# ArduinoUNOinBoard.net
KiCad netlist of a schematic drawn in EAGLE
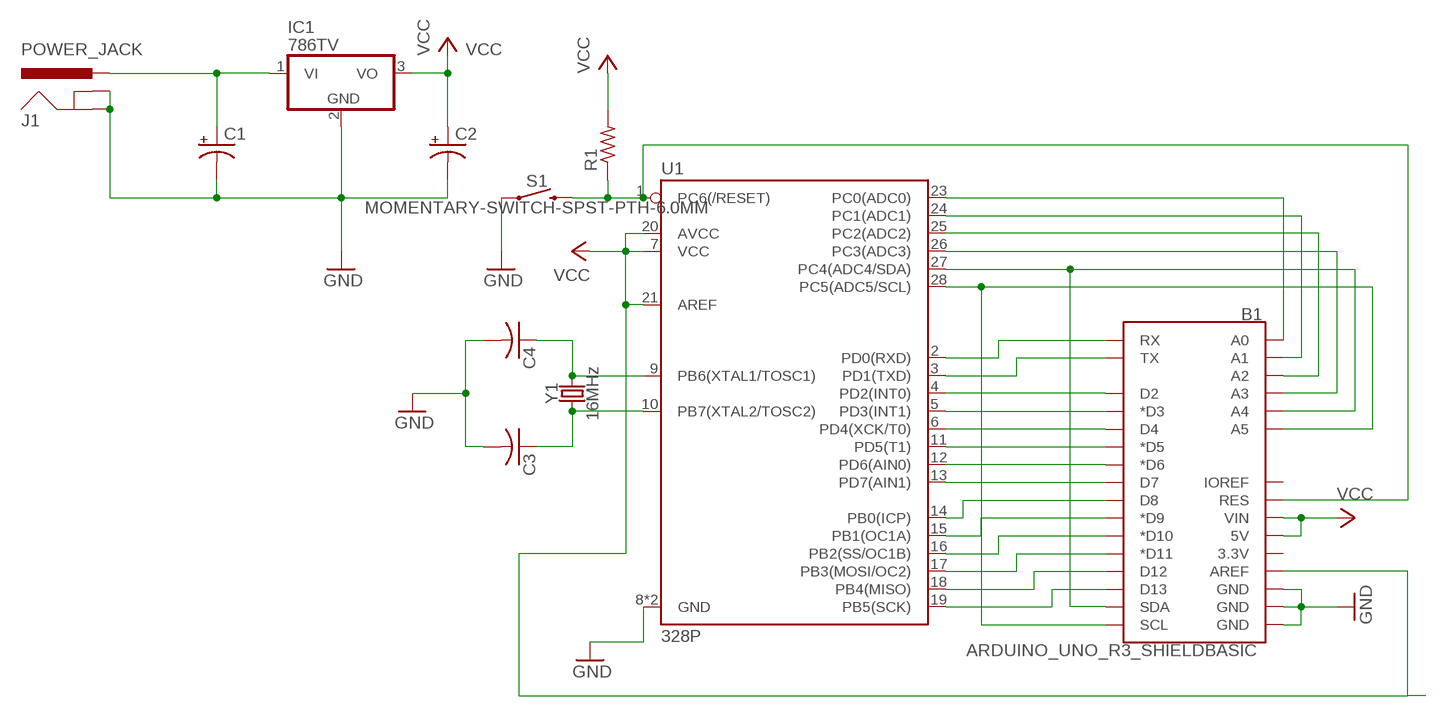
[diagram p0: schematic, sheet 1]

(export (version "E")
  (design (tool "Eeschema 10.0.6"))
  (components
    (comp (ref "B1")
      (value "ARDUINO_UNO_R3_SHIELDBASIC")
      (footprint "eagle-import:UNO_R3_SHIELD")
      (libsource (lib "eagle-import") (part "ARDUINO_UNO_R3_SHIELDBASIC"))
    )
    (comp (ref "C1")
      (value "CPOL-USE2,5-6E")
      (footprint "eagle-import:E2,5-6E")
      (libsource (lib "eagle-import") (part "CPOL-USE2,5-6E"))
    )
    (comp (ref "C2")
      (value "CPOL-USE2,5-6E")
      (footprint "eagle-import:E2,5-6E")
      (libsource (lib "eagle-import") (part "CPOL-USE2,5-6E"))
    )
    (comp (ref "C3")
      (value "C-US025-024X044")
      (footprint "eagle-import:C025-024X044")
      (libsource (lib "eagle-import") (part "C-US025-024X044"))
    )
    (comp (ref "C4")
      (value "C-US025-024X044")
      (footprint "eagle-import:C025-024X044")
      (libsource (lib "eagle-import") (part "C-US025-024X044"))
    )
    (comp (ref "IC1")
      (value "786TV")
      (footprint "eagle-import:TO220V")
      (libsource (lib "eagle-import") (part "78TV6"))
    )
    (comp (ref "J1")
      (value "POWER_JACK")
      (footprint "eagle-import:POWER_JACK_PTH")
      (libsource (lib "eagle-import") (part "POWER_JACK"))
    )
    (comp (ref "R1")
      (value "R-US_0204/7")
      (footprint "eagle-import:0204_7")
      (libsource (lib "eagle-import") (part "R-US_0204/7"))
    )
    (comp (ref "S1")
      (value "MOMENTARY-SWITCH-SPST-PTH-6.0MM")
      (footprint "eagle-import:TACTILE_SWITCH_PTH_6.0MM")
      (libsource (lib "eagle-import") (part "MOMENTARY-SWITCH-SPST-PTH-6.0MM"))
    )
    (comp (ref "U1")
      (value "328P")
      (footprint "eagle-import:DIP28")
      (libsource (lib "eagle-import") (part "ATMEGA328P_PDIP"))
    )
    (comp (ref "Y1")
      (value "16MHz")
      (footprint "eagle-import:HC49US")
      (libsource (lib "eagle-import") (part "CRYSTAL-16MHZPTH-HC49US"))
    )
  )
  (nets
    (net (code "1") (name "GND") (class "Default")
      (node (ref "B1") (pin "GND@0") (pinfunction "GND_GND@0") (pintype "bidirectional"))
      (node (ref "B1") (pin "GND@1") (pinfunction "GND_GND@1") (pintype "bidirectional"))
      (node (ref "B1") (pin "GND@2") (pinfunction "GND_GND@2") (pintype "bidirectional"))
      (node (ref "C1") (pin "-") (pinfunction "-_-") (pintype "passive"))
      (node (ref "C2") (pin "-") (pinfunction "-_-") (pintype "passive"))
      (node (ref "C3") (pin "2") (pinfunction "2_2") (pintype "passive"))
      (node (ref "C4") (pin "2") (pinfunction "2_2") (pintype "passive"))
      (node (ref "IC1") (pin "2") (pinfunction "GND_2") (pintype "passive"))
      (node (ref "J1") (pin "GND") (pinfunction "GND_GND") (pintype "bidirectional"))
      (node (ref "J1") (pin "GNDBREAK") (pinfunction "GNDBREAK_GNDBREAK") (pintype "bidirectional"))
      (node (ref "S1") (pin "1") (pinfunction "1_1") (pintype "passive"))
      (node (ref "U1") (pin "22") (pinfunction "GND_22") (pintype "bidirectional"))
      (node (ref "U1") (pin "8") (pinfunction "GND_8") (pintype "bidirectional"))
    )
    (net (code "2") (name "Net-(B1-*D3)") (class "Default")
      (node (ref "B1") (pin "D3") (pinfunction "*D3_D3") (pintype "bidirectional"))
      (node (ref "U1") (pin "5") (pinfunction "PD3(INT1)_5") (pintype "bidirectional"))
    )
    (net (code "3") (name "Net-(B1-*D5)") (class "Default")
      (node (ref "B1") (pin "D5") (pinfunction "*D5_D5") (pintype "bidirectional"))
      (node (ref "U1") (pin "11") (pinfunction "PD5(T1)_11") (pintype "bidirectional"))
    )
    (net (code "4") (name "Net-(B1-*D6)") (class "Default")
      (node (ref "B1") (pin "D6") (pinfunction "*D6_D6") (pintype "bidirectional"))
      (node (ref "U1") (pin "12") (pinfunction "PD6(AIN0)_12") (pintype "bidirectional"))
    )
    (net (code "5") (name "Net-(B1-*D9)") (class "Default")
      (node (ref "B1") (pin "D9") (pinfunction "*D9_D9") (pintype "bidirectional"))
      (node (ref "U1") (pin "15") (pinfunction "PB1(OC1A)_15") (pintype "bidirectional"))
    )
    (net (code "6") (name "Net-(B1-*D10)") (class "Default")
      (node (ref "B1") (pin "D10") (pinfunction "*D10_D10") (pintype "bidirectional"))
      (node (ref "U1") (pin "16") (pinfunction "PB2(SS/OC1B)_16") (pintype "bidirectional"))
    )
    (net (code "7") (name "Net-(B1-*D11)") (class "Default")
      (node (ref "B1") (pin "D11") (pinfunction "*D11_D11") (pintype "bidirectional"))
      (node (ref "U1") (pin "17") (pinfunction "PB3(MOSI/OC2)_17") (pintype "bidirectional"))
    )
    (net (code "8") (name "Net-(IC1-VI)") (class "Default")
      (node (ref "C1") (pin "+") (pinfunction "+_+") (pintype "passive"))
      (node (ref "IC1") (pin "1") (pinfunction "VI_1") (pintype "input"))
      (node (ref "J1") (pin "PWR") (pinfunction "PWR_PWR") (pintype "bidirectional"))
    )
    (net (code "9") (name "Net-(S1-2)") (class "Default")
      (node (ref "B1") (pin "RES") (pinfunction "RES_RES") (pintype "bidirectional"))
      (node (ref "R1") (pin "1") (pinfunction "1_1") (pintype "passive"))
      (node (ref "S1") (pin "3") (pinfunction "2_3") (pintype "passive"))
      (node (ref "U1") (pin "1") (pinfunction "PC6(/RESET)_1") (pintype "bidirectional"))
    )
    (net (code "10") (name "Net-(U1-PB0(ICP))") (class "Default")
      (node (ref "B1") (pin "D8") (pinfunction "D8_D8") (pintype "bidirectional"))
      (node (ref "U1") (pin "14") (pinfunction "PB0(ICP)_14") (pintype "bidirectional"))
    )
    (net (code "11") (name "Net-(U1-PB4(MISO))") (class "Default")
      (node (ref "B1") (pin "D12") (pinfunction "D12_D12") (pintype "bidirectional"))
      (node (ref "U1") (pin "18") (pinfunction "PB4(MISO)_18") (pintype "bidirectional"))
    )
    (net (code "12") (name "Net-(U1-PB5(SCK))") (class "Default")
      (node (ref "B1") (pin "D13") (pinfunction "D13_D13") (pintype "bidirectional"))
      (node (ref "U1") (pin "19") (pinfunction "PB5(SCK)_19") (pintype "bidirectional"))
    )
    (net (code "13") (name "Net-(U1-PB6(XTAL1{slash}TOSC1))") (class "Default")
      (node (ref "C4") (pin "1") (pinfunction "1_1") (pintype "passive"))
      (node (ref "U1") (pin "9") (pinfunction "PB6(XTAL1/TOSC1)_9") (pintype "bidirectional"))
      (node (ref "Y1") (pin "2") (pinfunction "2_2") (pintype "passive"))
    )
    (net (code "14") (name "Net-(U1-PB7(XTAL2{slash}TOSC2))") (class "Default")
      (node (ref "C3") (pin "1") (pinfunction "1_1") (pintype "passive"))
      (node (ref "U1") (pin "10") (pinfunction "PB7(XTAL2/TOSC2)_10") (pintype "bidirectional"))
      (node (ref "Y1") (pin "1") (pinfunction "1_1") (pintype "passive"))
    )
    (net (code "15") (name "Net-(U1-PC0(ADC0))") (class "Default")
      (node (ref "B1") (pin "A0") (pinfunction "A0_A0") (pintype "bidirectional"))
      (node (ref "U1") (pin "23") (pinfunction "PC0(ADC0)_23") (pintype "bidirectional"))
    )
    (net (code "16") (name "Net-(U1-PC1(ADC1))") (class "Default")
      (node (ref "B1") (pin "A1") (pinfunction "A1_A1") (pintype "bidirectional"))
      (node (ref "U1") (pin "24") (pinfunction "PC1(ADC1)_24") (pintype "bidirectional"))
    )
    (net (code "17") (name "Net-(U1-PC2(ADC2))") (class "Default")
      (node (ref "B1") (pin "A2") (pinfunction "A2_A2") (pintype "bidirectional"))
      (node (ref "U1") (pin "25") (pinfunction "PC2(ADC2)_25") (pintype "bidirectional"))
    )
    (net (code "18") (name "Net-(U1-PC3(ADC3))") (class "Default")
      (node (ref "B1") (pin "A3") (pinfunction "A3_A3") (pintype "bidirectional"))
      (node (ref "U1") (pin "26") (pinfunction "PC3(ADC3)_26") (pintype "bidirectional"))
    )
    (net (code "19") (name "Net-(U1-PC4(ADC4{slash}SDA))") (class "Default")
      (node (ref "B1") (pin "A4") (pinfunction "A4_A4") (pintype "bidirectional"))
      (node (ref "B1") (pin "SDA") (pinfunction "SDA_SDA") (pintype "bidirectional"))
      (node (ref "U1") (pin "27") (pinfunction "PC4(ADC4/SDA)_27") (pintype "bidirectional"))
    )
    (net (code "20") (name "Net-(U1-PC5(ADC5{slash}SCL))") (class "Default")
      (node (ref "B1") (pin "A5") (pinfunction "A5_A5") (pintype "bidirectional"))
      (node (ref "B1") (pin "SCL") (pinfunction "SCL_SCL") (pintype "bidirectional"))
      (node (ref "U1") (pin "28") (pinfunction "PC5(ADC5/SCL)_28") (pintype "bidirectional"))
    )
    (net (code "21") (name "Net-(U1-PD0(RXD))") (class "Default")
      (node (ref "B1") (pin "RX") (pinfunction "RX_RX") (pintype "bidirectional"))
      (node (ref "U1") (pin "2") (pinfunction "PD0(RXD)_2") (pintype "bidirectional"))
    )
    (net (code "22") (name "Net-(U1-PD1(TXD))") (class "Default")
      (node (ref "B1") (pin "TX") (pinfunction "TX_TX") (pintype "bidirectional"))
      (node (ref "U1") (pin "3") (pinfunction "PD1(TXD)_3") (pintype "bidirectional"))
    )
    (net (code "23") (name "Net-(U1-PD2(INT0))") (class "Default")
      (node (ref "B1") (pin "D2") (pinfunction "D2_D2") (pintype "bidirectional"))
      (node (ref "U1") (pin "4") (pinfunction "PD2(INT0)_4") (pintype "bidirectional"))
    )
    (net (code "24") (name "Net-(U1-PD4(XCK{slash}T0))") (class "Default")
      (node (ref "B1") (pin "D4") (pinfunction "D4_D4") (pintype "bidirectional"))
      (node (ref "U1") (pin "6") (pinfunction "PD4(XCK/T0)_6") (pintype "bidirectional"))
    )
    (net (code "25") (name "Net-(U1-PD7(AIN1))") (class "Default")
      (node (ref "B1") (pin "D7") (pinfunction "D7_D7") (pintype "bidirectional"))
      (node (ref "U1") (pin "13") (pinfunction "PD7(AIN1)_13") (pintype "bidirectional"))
    )
    (net (code "26") (name "VCC") (class "Default")
      (node (ref "B1") (pin "5V") (pinfunction "5V_5V") (pintype "bidirectional"))
      (node (ref "B1") (pin "AREF") (pinfunction "AREF_AREF") (pintype "bidirectional"))
      (node (ref "B1") (pin "VIN") (pinfunction "VIN_VIN") (pintype "bidirectional"))
      (node (ref "C2") (pin "+") (pinfunction "+_+") (pintype "passive"))
      (node (ref "IC1") (pin "3") (pinfunction "VO_3") (pintype "passive"))
      (node (ref "R1") (pin "2") (pinfunction "2_2") (pintype "passive"))
      (node (ref "U1") (pin "20") (pinfunction "AVCC_20") (pintype "bidirectional"))
      (node (ref "U1") (pin "21") (pinfunction "AREF_21") (pintype "bidirectional"))
      (node (ref "U1") (pin "7") (pinfunction "VCC_7") (pintype "bidirectional"))
    )
    (net (code "27") (name "unconnected-(B1-Pad3.3V)") (class "Default")
      (node (ref "B1") (pin "3.3V") (pinfunction "3.3V_3.3V") (pintype "bidirectional"))
    )
    (net (code "28") (name "unconnected-(B1-PadIOREF)") (class "Default")
      (node (ref "B1") (pin "IOREF") (pinfunction "IOREF_IOREF") (pintype "bidirectional"))
    )
  )
)
